# MCU.net
KiCad netlist of a schematic drawn in Altium Designer
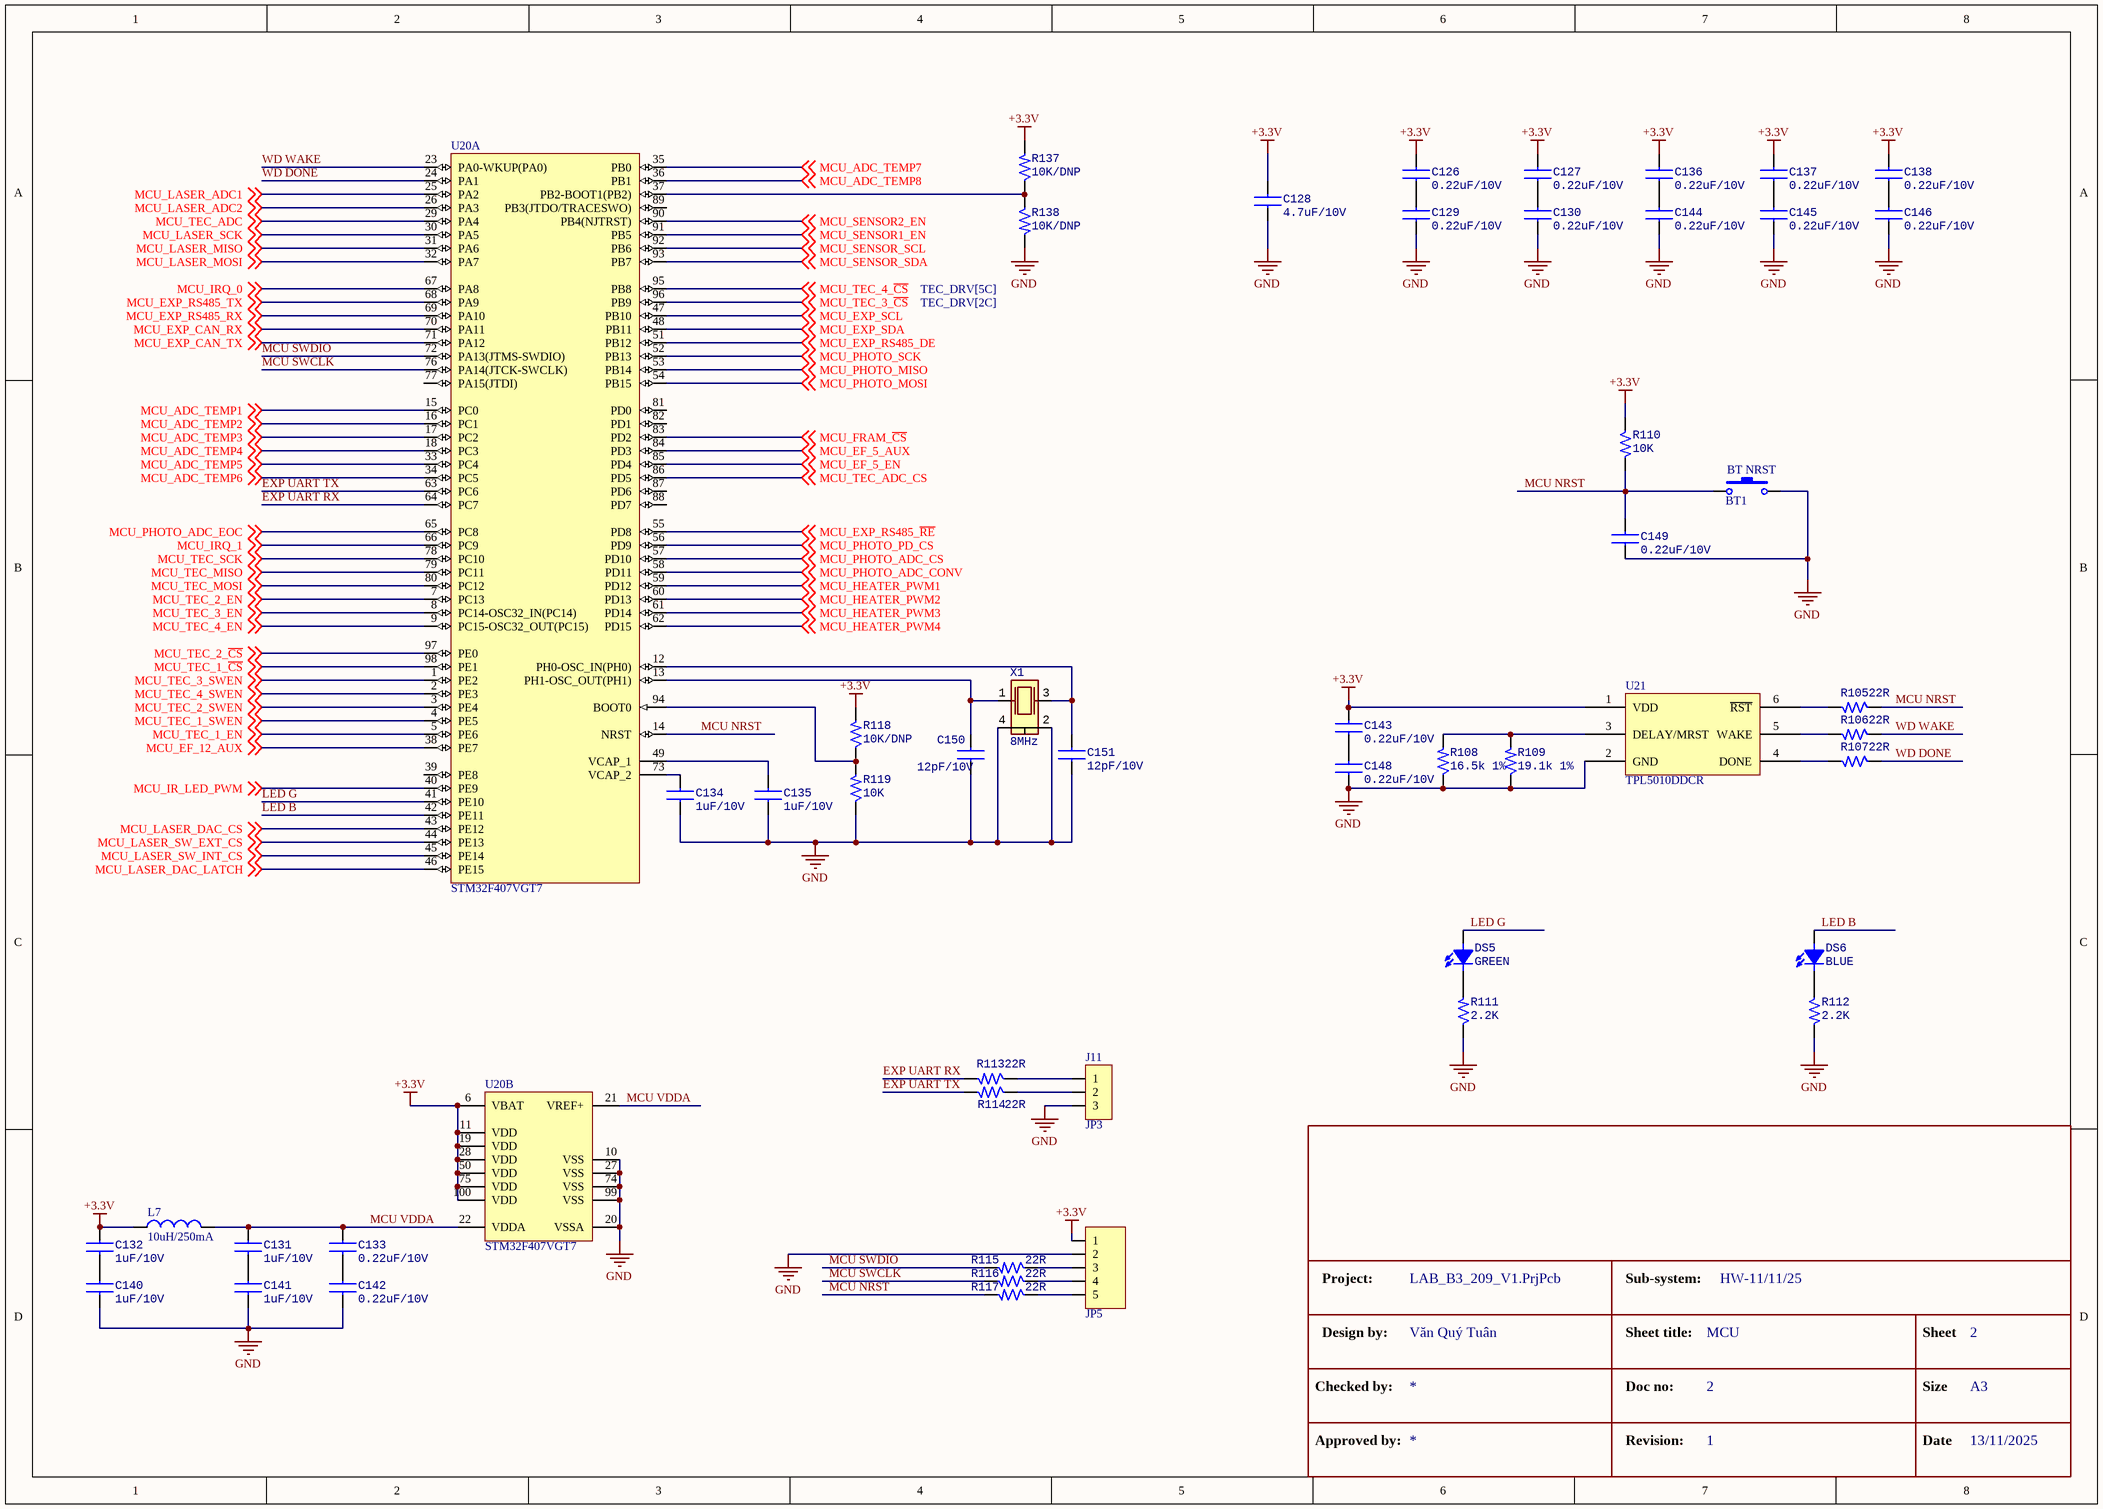
[diagram p0: MCU.SchDoc]

(export (version "E")
  (design (tool "Eeschema 10.0.6"))
  (components
    (comp (ref "BT1")
      (value "BT NRST")
      (footprint "SW-SMD")
      (description "Switch")
      (fields (field (name "PUBLISHER") "Altium Limited"))
      (libsource (lib "Schematic") (part "SW-SMD"))
    )
    (comp (ref "C126")
      (value "0.22uF/10V")
      (footprint "CAP-CER-0603")
      (libsource (lib "ID") (part "CAP-CER"))
    )
    (comp (ref "C127")
      (value "0.22uF/10V")
      (footprint "CAP-CER-0603")
      (libsource (lib "ID") (part "CAP-CER"))
    )
    (comp (ref "C128") (value "4.7uF/10V") (footprint "CAP-CER-0603") (libsource (lib "ID") (part "CAP-CER")))
    (comp (ref "C129")
      (value "0.22uF/10V")
      (footprint "CAP-CER-0603")
      (libsource (lib "ID") (part "CAP-CER"))
    )
    (comp (ref "C130")
      (value "0.22uF/10V")
      (footprint "CAP-CER-0603")
      (libsource (lib "ID") (part "CAP-CER"))
    )
    (comp (ref "C131") (value "1uF/10V") (footprint "CAP-CER-0603") (libsource (lib "ID") (part "CAP-CER")))
    (comp (ref "C132") (value "1uF/10V") (footprint "CAP-CER-0603") (libsource (lib "ID") (part "CAP-CER")))
    (comp (ref "C133")
      (value "0.22uF/10V")
      (footprint "CAP-CER-0603")
      (libsource (lib "ID") (part "CAP-CER"))
    )
    (comp (ref "C134") (value "1uF/10V") (footprint "CAP-CER-0603") (libsource (lib "ID") (part "CAP-CER")))
    (comp (ref "C135") (value "1uF/10V") (footprint "CAP-CER-0603") (libsource (lib "ID") (part "CAP-CER")))
    (comp (ref "C136")
      (value "0.22uF/10V")
      (footprint "CAP-CER-0603")
      (libsource (lib "ID") (part "CAP-CER"))
    )
    (comp (ref "C137")
      (value "0.22uF/10V")
      (footprint "CAP-CER-0603")
      (libsource (lib "ID") (part "CAP-CER"))
    )
    (comp (ref "C138")
      (value "0.22uF/10V")
      (footprint "CAP-CER-0603")
      (libsource (lib "ID") (part "CAP-CER"))
    )
    (comp (ref "C140") (value "1uF/10V") (footprint "CAP-CER-0603") (libsource (lib "ID") (part "CAP-CER")))
    (comp (ref "C141") (value "1uF/10V") (footprint "CAP-CER-0603") (libsource (lib "ID") (part "CAP-CER")))
    (comp (ref "C142")
      (value "0.22uF/10V")
      (footprint "CAP-CER-0603")
      (libsource (lib "ID") (part "CAP-CER"))
    )
    (comp (ref "C143")
      (value "0.22uF/10V")
      (footprint "CAP-CER-0603")
      (libsource (lib "ID") (part "CAP-CER"))
    )
    (comp (ref "C144")
      (value "0.22uF/10V")
      (footprint "CAP-CER-0603")
      (libsource (lib "ID") (part "CAP-CER"))
    )
    (comp (ref "C145")
      (value "0.22uF/10V")
      (footprint "CAP-CER-0603")
      (libsource (lib "ID") (part "CAP-CER"))
    )
    (comp (ref "C146")
      (value "0.22uF/10V")
      (footprint "CAP-CER-0603")
      (libsource (lib "ID") (part "CAP-CER"))
    )
    (comp (ref "C148")
      (value "0.22uF/10V")
      (footprint "CAP-CER-0603")
      (libsource (lib "ID") (part "CAP-CER"))
    )
    (comp (ref "C149")
      (value "0.22uF/10V")
      (footprint "CAP-CER-0603")
      (libsource (lib "ID") (part "CAP-CER"))
    )
    (comp (ref "C150") (value "12pF/10V") (footprint "CAP-CER-0603") (libsource (lib "ID") (part "CAP-CER")))
    (comp (ref "C151") (value "12pF/10V") (footprint "CAP-CER-0603") (libsource (lib "ID") (part "CAP-CER")))
    (comp (ref "DS5") (value "GREEN") (footprint "LED-SMD-0603") (libsource (lib "ID") (part "LED")))
    (comp (ref "DS6") (value "BLUE") (footprint "LED-SMD-0603") (libsource (lib "ID") (part "LED")))
    (comp (ref "J6")
      (value "JP5")
      (footprint "JP 1x5 CT")
      (description "1X5 2.54")
      (libsource (lib "Jump") (part "JP 1x5 2.54 Cai Thang"))
    )
    (comp (ref "J11")
      (value "JP3")
      (footprint "JP 1x3 CT")
      (description "1X3 2.54")
      (libsource (lib "Jump") (part "JP 1x3 2.54 Cai Thang"))
    )
    (comp (ref "L7")
      (value "10uH/250mA")
      (footprint "INDUCT-SMD-0603")
      (fields (field (name "MP") "LQM18PZ2R2MFHD") (field (name "MF") "Murata"))
      (libsource (lib "ID") (part "INDUCT-SMD"))
    )
    (comp (ref "R105") (value "22R") (footprint "RES-SMD-0603") (libsource (lib "ID") (part "RES-SMD")))
    (comp (ref "R106") (value "22R") (footprint "RES-SMD-0603") (libsource (lib "ID") (part "RES-SMD")))
    (comp (ref "R107") (value "22R") (footprint "RES-SMD-0603") (libsource (lib "ID") (part "RES-SMD")))
    (comp (ref "R108") (value "16.5k 1%") (footprint "RES-SMD-0603") (libsource (lib "ID") (part "RES-SMD")))
    (comp (ref "R109") (value "19.1k 1%") (footprint "RES-SMD-0603") (libsource (lib "ID") (part "RES-SMD")))
    (comp (ref "R110") (value "10K") (footprint "RES-SMD-0603") (libsource (lib "ID") (part "RES-SMD")))
    (comp (ref "R111") (value "2.2K") (footprint "RES-SMD-0603") (libsource (lib "ID") (part "RES-SMD")))
    (comp (ref "R112") (value "2.2K") (footprint "RES-SMD-0603") (libsource (lib "ID") (part "RES-SMD")))
    (comp (ref "R113") (value "22R") (footprint "RES-SMD-0603") (libsource (lib "ID") (part "RES-SMD")))
    (comp (ref "R114") (value "22R") (footprint "RES-SMD-0603") (libsource (lib "ID") (part "RES-SMD")))
    (comp (ref "R115") (value "22R") (footprint "RES-SMD-0603") (libsource (lib "ID") (part "RES-SMD")))
    (comp (ref "R116") (value "22R") (footprint "RES-SMD-0603") (libsource (lib "ID") (part "RES-SMD")))
    (comp (ref "R117") (value "22R") (footprint "RES-SMD-0603") (libsource (lib "ID") (part "RES-SMD")))
    (comp (ref "R118") (value "10K/DNP") (footprint "RES-SMD-0603") (libsource (lib "ID") (part "RES-SMD")))
    (comp (ref "R119") (value "10K") (footprint "RES-SMD-0603") (libsource (lib "ID") (part "RES-SMD")))
    (comp (ref "R137") (value "10K/DNP") (footprint "RES-SMD-0603") (libsource (lib "ID") (part "RES-SMD")))
    (comp (ref "R138") (value "10K/DNP") (footprint "RES-SMD-0603") (libsource (lib "ID") (part "RES-SMD")))
    (comp (ref "U20")
      (value "STM32F407VGT7")
      (footprint "STM-LQFP100_V")
      (fields (field (name "MANUFACTURER") "STMicroelectronics"))
      (libsource (lib "STMicroelectronics STM32 F4") (part "STM32F407VGT7"))
    )
    (comp (ref "U21")
      (value "TPL5010DDCR")
      (footprint "TPL5010DDCR")
      (libsource (lib "LAB_B3_209_V1") (part "TPL5010DDCR"))
    )
    (comp (ref "X1")
      (value "8MHz")
      (footprint "CRYSTAL-4POS-3.2x2.5")
      (description "Crystal, 8 MHz, -30 to 85 degC, 3.2 x 2.5 x 0.9 mm SMD")
      (libsource (lib "ID") (part "CRYSTAL-4POS"))
    )
  )
  (nets
    (net (code "1") (name "+3.3V") (class "Default")
      (node (ref "C126") (pin "1") (pinfunction "1_1") (pintype "passive"))
      (node (ref "C127") (pin "1") (pinfunction "1_1") (pintype "passive"))
      (node (ref "C128") (pin "1") (pinfunction "1_1") (pintype "passive"))
      (node (ref "C132") (pin "1") (pinfunction "1_1") (pintype "passive"))
      (node (ref "C136") (pin "1") (pinfunction "1_1") (pintype "passive"))
      (node (ref "C137") (pin "1") (pinfunction "1_1") (pintype "passive"))
      (node (ref "C138") (pin "1") (pinfunction "1_1") (pintype "passive"))
      (node (ref "C143") (pin "1") (pinfunction "1_1") (pintype "passive"))
      (node (ref "J6") (pin "1") (pinfunction "1_1") (pintype "passive"))
      (node (ref "L7") (pin "1") (pinfunction "1_1") (pintype "passive"))
      (node (ref "R110") (pin "1") (pinfunction "1_1") (pintype "passive"))
      (node (ref "R118") (pin "2") (pinfunction "2_2") (pintype "passive"))
      (node (ref "R137") (pin "2") (pinfunction "2_2") (pintype "passive"))
      (node (ref "U20") (pin "100") (pinfunction "VDD_100") (pintype "power_in"))
      (node (ref "U20") (pin "11") (pinfunction "VDD_11") (pintype "power_in"))
      (node (ref "U20") (pin "19") (pinfunction "VDD_19") (pintype "power_in"))
      (node (ref "U20") (pin "28") (pinfunction "VDD_28") (pintype "power_in"))
      (node (ref "U20") (pin "50") (pinfunction "VDD_50") (pintype "power_in"))
      (node (ref "U20") (pin "6") (pinfunction "VBAT_6") (pintype "power_in"))
      (node (ref "U20") (pin "75") (pinfunction "VDD_75") (pintype "power_in"))
      (node (ref "U21") (pin "1") (pinfunction "VDD_1") (pintype "passive"))
    )
    (net (code "2") (name "/EXP UART RX") (class "Default")
      (node (ref "R113") (pin "2") (pinfunction "2_2") (pintype "passive"))
      (node (ref "U20") (pin "64") (pinfunction "PC7_64") (pintype "bidirectional"))
    )
    (net (code "3") (name "/EXP UART TX") (class "Default")
      (node (ref "R114") (pin "2") (pinfunction "2_2") (pintype "passive"))
      (node (ref "U20") (pin "63") (pinfunction "PC6_63") (pintype "bidirectional"))
    )
    (net (code "4") (name "/LED B") (class "Default")
      (node (ref "DS6") (pin "A") (pinfunction "A_A") (pintype "passive"))
      (node (ref "U20") (pin "42") (pinfunction "PE11_42") (pintype "bidirectional"))
    )
    (net (code "5") (name "/LED G") (class "Default")
      (node (ref "DS5") (pin "A") (pinfunction "A_A") (pintype "passive"))
      (node (ref "U20") (pin "41") (pinfunction "PE10_41") (pintype "bidirectional"))
    )
    (net (code "6") (name "/MCU NRST") (class "Default")
      (node (ref "BT1") (pin "1") (pinfunction "1_1") (pintype "passive"))
      (node (ref "C149") (pin "1") (pinfunction "1_1") (pintype "passive"))
      (node (ref "R105") (pin "1") (pinfunction "1_1") (pintype "passive"))
      (node (ref "R110") (pin "2") (pinfunction "2_2") (pintype "passive"))
      (node (ref "R117") (pin "2") (pinfunction "2_2") (pintype "passive"))
      (node (ref "U20") (pin "14") (pinfunction "NRST_14") (pintype "bidirectional"))
    )
    (net (code "7") (name "/MCU SWCLK") (class "Default")
      (node (ref "R116") (pin "2") (pinfunction "2_2") (pintype "passive"))
      (node (ref "U20") (pin "76") (pinfunction "PA14(JTCK-SWCLK)_76") (pintype "bidirectional"))
    )
    (net (code "8") (name "/MCU SWDIO") (class "Default")
      (node (ref "R115") (pin "2") (pinfunction "2_2") (pintype "passive"))
      (node (ref "U20") (pin "72") (pinfunction "PA13(JTMS-SWDIO)_72") (pintype "bidirectional"))
    )
    (net (code "9") (name "/MCU VDDA") (class "Default")
      (node (ref "C131") (pin "1") (pinfunction "1_1") (pintype "passive"))
      (node (ref "C133") (pin "1") (pinfunction "1_1") (pintype "passive"))
      (node (ref "L7") (pin "2") (pinfunction "2_2") (pintype "passive"))
      (node (ref "U20") (pin "21") (pinfunction "VREF+_21") (pintype "power_in"))
      (node (ref "U20") (pin "22") (pinfunction "VDDA_22") (pintype "power_in"))
    )
    (net (code "10") (name "/WD DONE") (class "Default")
      (node (ref "R107") (pin "1") (pinfunction "1_1") (pintype "passive"))
      (node (ref "U20") (pin "24") (pinfunction "PA1_24") (pintype "bidirectional"))
    )
    (net (code "11") (name "/WD WAKE") (class "Default")
      (node (ref "R106") (pin "1") (pinfunction "1_1") (pintype "passive"))
      (node (ref "U20") (pin "23") (pinfunction "PA0-WKUP(PA0)_23") (pintype "bidirectional"))
    )
    (net (code "12") (name "GND") (class "Default")
      (node (ref "BT1") (pin "2") (pinfunction "2_2") (pintype "passive"))
      (node (ref "C128") (pin "2") (pinfunction "2_2") (pintype "passive"))
      (node (ref "C129") (pin "2") (pinfunction "2_2") (pintype "passive"))
      (node (ref "C130") (pin "2") (pinfunction "2_2") (pintype "passive"))
      (node (ref "C134") (pin "2") (pinfunction "2_2") (pintype "passive"))
      (node (ref "C135") (pin "2") (pinfunction "2_2") (pintype "passive"))
      (node (ref "C140") (pin "2") (pinfunction "2_2") (pintype "passive"))
      (node (ref "C141") (pin "2") (pinfunction "2_2") (pintype "passive"))
      (node (ref "C142") (pin "2") (pinfunction "2_2") (pintype "passive"))
      (node (ref "C144") (pin "2") (pinfunction "2_2") (pintype "passive"))
      (node (ref "C145") (pin "2") (pinfunction "2_2") (pintype "passive"))
      (node (ref "C146") (pin "2") (pinfunction "2_2") (pintype "passive"))
      (node (ref "C148") (pin "2") (pinfunction "2_2") (pintype "passive"))
      (node (ref "C149") (pin "2") (pinfunction "2_2") (pintype "passive"))
      (node (ref "C150") (pin "2") (pinfunction "2_2") (pintype "passive"))
      (node (ref "C151") (pin "2") (pinfunction "2_2") (pintype "passive"))
      (node (ref "J11") (pin "3") (pinfunction "3_3") (pintype "passive"))
      (node (ref "J6") (pin "2") (pinfunction "2_2") (pintype "passive"))
      (node (ref "R108") (pin "1") (pinfunction "1_1") (pintype "passive"))
      (node (ref "R109") (pin "1") (pinfunction "1_1") (pintype "passive"))
      (node (ref "R111") (pin "1") (pinfunction "1_1") (pintype "passive"))
      (node (ref "R112") (pin "2") (pinfunction "2_2") (pintype "passive"))
      (node (ref "R119") (pin "1") (pinfunction "1_1") (pintype "passive"))
      (node (ref "R138") (pin "2") (pinfunction "2_2") (pintype "passive"))
      (node (ref "U20") (pin "10") (pinfunction "VSS_10") (pintype "power_in"))
      (node (ref "U20") (pin "20") (pinfunction "VSSA_20") (pintype "power_in"))
      (node (ref "U20") (pin "27") (pinfunction "VSS_27") (pintype "power_in"))
      (node (ref "U20") (pin "74") (pinfunction "VSS_74") (pintype "power_in"))
      (node (ref "U20") (pin "99") (pinfunction "VSS_99") (pintype "power_in"))
      (node (ref "U21") (pin "2") (pinfunction "GND_2") (pintype "passive"))
      (node (ref "X1") (pin "2") (pinfunction "2_2") (pintype "passive"))
      (node (ref "X1") (pin "4") (pinfunction "4_4") (pintype "passive"))
    )
    (net (code "13") (name "MCU_ADC_TEMP1") (class "Default")
      (node (ref "U20") (pin "15") (pinfunction "PC0_15") (pintype "bidirectional"))
    )
    (net (code "14") (name "MCU_ADC_TEMP2") (class "Default")
      (node (ref "U20") (pin "16") (pinfunction "PC1_16") (pintype "bidirectional"))
    )
    (net (code "15") (name "MCU_ADC_TEMP3") (class "Default")
      (node (ref "U20") (pin "17") (pinfunction "PC2_17") (pintype "bidirectional"))
    )
    (net (code "16") (name "MCU_ADC_TEMP4") (class "Default")
      (node (ref "U20") (pin "18") (pinfunction "PC3_18") (pintype "bidirectional"))
    )
    (net (code "17") (name "MCU_ADC_TEMP5") (class "Default")
      (node (ref "U20") (pin "33") (pinfunction "PC4_33") (pintype "bidirectional"))
    )
    (net (code "18") (name "MCU_ADC_TEMP6") (class "Default")
      (node (ref "U20") (pin "34") (pinfunction "PC5_34") (pintype "bidirectional"))
    )
    (net (code "19") (name "MCU_ADC_TEMP7") (class "Default")
      (node (ref "U20") (pin "35") (pinfunction "PB0_35") (pintype "bidirectional"))
    )
    (net (code "20") (name "MCU_ADC_TEMP8") (class "Default")
      (node (ref "U20") (pin "36") (pinfunction "PB1_36") (pintype "bidirectional"))
    )
    (net (code "21") (name "MCU_EF_5_AUX") (class "Default")
      (node (ref "U20") (pin "84") (pinfunction "PD3_84") (pintype "bidirectional"))
    )
    (net (code "22") (name "MCU_EF_5_EN") (class "Default")
      (node (ref "U20") (pin "85") (pinfunction "PD4_85") (pintype "bidirectional"))
    )
    (net (code "23") (name "MCU_EF_12_AUX") (class "Default")
      (node (ref "U20") (pin "38") (pinfunction "PE7_38") (pintype "bidirectional"))
    )
    (net (code "24") (name "MCU_EXP_CAN_RX") (class "Default")
      (node (ref "U20") (pin "70") (pinfunction "PA11_70") (pintype "bidirectional"))
    )
    (net (code "25") (name "MCU_EXP_CAN_TX") (class "Default")
      (node (ref "U20") (pin "71") (pinfunction "PA12_71") (pintype "bidirectional"))
    )
    (net (code "26") (name "MCU_EXP_RS485_DE") (class "Default")
      (node (ref "U20") (pin "51") (pinfunction "PB12_51") (pintype "bidirectional"))
    )
    (net (code "27") (name "MCU_EXP_RS485_RX") (class "Default")
      (node (ref "U20") (pin "69") (pinfunction "PA10_69") (pintype "bidirectional"))
    )
    (net (code "28") (name "MCU_EXP_RS485_TX") (class "Default")
      (node (ref "U20") (pin "68") (pinfunction "PA9_68") (pintype "bidirectional"))
    )
    (net (code "29") (name "MCU_EXP_RS485_~{RE}") (class "Default")
      (node (ref "U20") (pin "55") (pinfunction "PD8_55") (pintype "bidirectional"))
    )
    (net (code "30") (name "MCU_EXP_SCL") (class "Default")
      (node (ref "U20") (pin "47") (pinfunction "PB10_47") (pintype "bidirectional"))
    )
    (net (code "31") (name "MCU_EXP_SDA") (class "Default")
      (node (ref "U20") (pin "48") (pinfunction "PB11_48") (pintype "bidirectional"))
    )
    (net (code "32") (name "MCU_FRAM_~{CS}") (class "Default")
      (node (ref "U20") (pin "83") (pinfunction "PD2_83") (pintype "bidirectional"))
    )
    (net (code "33") (name "MCU_HEATER_PWM1") (class "Default")
      (node (ref "U20") (pin "59") (pinfunction "PD12_59") (pintype "bidirectional"))
    )
    (net (code "34") (name "MCU_HEATER_PWM2") (class "Default")
      (node (ref "U20") (pin "60") (pinfunction "PD13_60") (pintype "bidirectional"))
    )
    (net (code "35") (name "MCU_HEATER_PWM3") (class "Default")
      (node (ref "U20") (pin "61") (pinfunction "PD14_61") (pintype "bidirectional"))
    )
    (net (code "36") (name "MCU_HEATER_PWM4") (class "Default")
      (node (ref "U20") (pin "62") (pinfunction "PD15_62") (pintype "bidirectional"))
    )
    (net (code "37") (name "MCU_IRQ_0") (class "Default")
      (node (ref "U20") (pin "67") (pinfunction "PA8_67") (pintype "bidirectional"))
    )
    (net (code "38") (name "MCU_IRQ_1") (class "Default")
      (node (ref "U20") (pin "66") (pinfunction "PC9_66") (pintype "bidirectional"))
    )
    (net (code "39") (name "MCU_IR_LED_PWM") (class "Default")
      (node (ref "U20") (pin "40") (pinfunction "PE9_40") (pintype "bidirectional"))
    )
    (net (code "40") (name "MCU_LASER_ADC1") (class "Default")
      (node (ref "U20") (pin "25") (pinfunction "PA2_25") (pintype "bidirectional"))
    )
    (net (code "41") (name "MCU_LASER_ADC2") (class "Default")
      (node (ref "U20") (pin "26") (pinfunction "PA3_26") (pintype "bidirectional"))
    )
    (net (code "42") (name "MCU_LASER_DAC_CS") (class "Default")
      (node (ref "U20") (pin "43") (pinfunction "PE12_43") (pintype "bidirectional"))
    )
    (net (code "43") (name "MCU_LASER_DAC_LATCH") (class "Default")
      (node (ref "U20") (pin "46") (pinfunction "PE15_46") (pintype "bidirectional"))
    )
    (net (code "44") (name "MCU_LASER_MISO") (class "Default")
      (node (ref "U20") (pin "31") (pinfunction "PA6_31") (pintype "bidirectional"))
    )
    (net (code "45") (name "MCU_LASER_MOSI") (class "Default")
      (node (ref "U20") (pin "32") (pinfunction "PA7_32") (pintype "bidirectional"))
    )
    (net (code "46") (name "MCU_LASER_SCK") (class "Default")
      (node (ref "U20") (pin "30") (pinfunction "PA5_30") (pintype "bidirectional"))
    )
    (net (code "47") (name "MCU_LASER_SW_EXT_CS") (class "Default")
      (node (ref "U20") (pin "44") (pinfunction "PE13_44") (pintype "bidirectional"))
    )
    (net (code "48") (name "MCU_LASER_SW_INT_CS") (class "Default")
      (node (ref "U20") (pin "45") (pinfunction "PE14_45") (pintype "bidirectional"))
    )
    (net (code "49") (name "MCU_PHOTO_ADC_CONV") (class "Default")
      (node (ref "U20") (pin "58") (pinfunction "PD11_58") (pintype "bidirectional"))
    )
    (net (code "50") (name "MCU_PHOTO_ADC_CS") (class "Default")
      (node (ref "U20") (pin "57") (pinfunction "PD10_57") (pintype "bidirectional"))
    )
    (net (code "51") (name "MCU_PHOTO_ADC_EOC") (class "Default")
      (node (ref "U20") (pin "65") (pinfunction "PC8_65") (pintype "bidirectional"))
    )
    (net (code "52") (name "MCU_PHOTO_MISO") (class "Default")
      (node (ref "U20") (pin "53") (pinfunction "PB14_53") (pintype "bidirectional"))
    )
    (net (code "53") (name "MCU_PHOTO_MOSI") (class "Default")
      (node (ref "U20") (pin "54") (pinfunction "PB15_54") (pintype "bidirectional"))
    )
    (net (code "54") (name "MCU_PHOTO_PD_CS") (class "Default")
      (node (ref "U20") (pin "56") (pinfunction "PD9_56") (pintype "bidirectional"))
    )
    (net (code "55") (name "MCU_PHOTO_SCK") (class "Default")
      (node (ref "U20") (pin "52") (pinfunction "PB13_52") (pintype "bidirectional"))
    )
    (net (code "56") (name "MCU_SENSOR1_EN") (class "Default")
      (node (ref "U20") (pin "91") (pinfunction "PB5_91") (pintype "bidirectional"))
    )
    (net (code "57") (name "MCU_SENSOR2_EN") (class "Default")
      (node (ref "U20") (pin "90") (pinfunction "PB4(NJTRST)_90") (pintype "bidirectional"))
    )
    (net (code "58") (name "MCU_SENSOR_SCL") (class "Default")
      (node (ref "U20") (pin "92") (pinfunction "PB6_92") (pintype "bidirectional"))
    )
    (net (code "59") (name "MCU_SENSOR_SDA") (class "Default")
      (node (ref "U20") (pin "93") (pinfunction "PB7_93") (pintype "bidirectional"))
    )
    (net (code "60") (name "MCU_TEC_1_EN") (class "Default")
      (node (ref "U20") (pin "5") (pinfunction "PE6_5") (pintype "bidirectional"))
    )
    (net (code "61") (name "MCU_TEC_1_SWEN") (class "Default")
      (node (ref "U20") (pin "4") (pinfunction "PE5_4") (pintype "bidirectional"))
    )
    (net (code "62") (name "MCU_TEC_1_~{CS}") (class "Default")
      (node (ref "U20") (pin "98") (pinfunction "PE1_98") (pintype "bidirectional"))
    )
    (net (code "63") (name "MCU_TEC_2_EN") (class "Default")
      (node (ref "U20") (pin "7") (pinfunction "PC13_7") (pintype "bidirectional"))
    )
    (net (code "64") (name "MCU_TEC_2_SWEN") (class "Default")
      (node (ref "U20") (pin "3") (pinfunction "PE4_3") (pintype "bidirectional"))
    )
    (net (code "65") (name "MCU_TEC_2_~{CS}") (class "Default")
      (node (ref "U20") (pin "97") (pinfunction "PE0_97") (pintype "bidirectional"))
    )
    (net (code "66") (name "MCU_TEC_3_EN") (class "Default")
      (node (ref "U20") (pin "8") (pinfunction "PC14-OSC32_IN(PC14)_8") (pintype "bidirectional"))
    )
    (net (code "67") (name "MCU_TEC_3_SWEN") (class "Default")
      (node (ref "U20") (pin "1") (pinfunction "PE2_1") (pintype "bidirectional"))
    )
    (net (code "68") (name "MCU_TEC_3_~{CS}") (class "Default")
      (node (ref "U20") (pin "96") (pinfunction "PB9_96") (pintype "bidirectional"))
    )
    (net (code "69") (name "MCU_TEC_4_EN") (class "Default")
      (node (ref "U20") (pin "9") (pinfunction "PC15-OSC32_OUT(PC15)_9") (pintype "bidirectional"))
    )
    (net (code "70") (name "MCU_TEC_4_SWEN") (class "Default")
      (node (ref "U20") (pin "2") (pinfunction "PE3_2") (pintype "bidirectional"))
    )
    (net (code "71") (name "MCU_TEC_4_~{CS}") (class "Default")
      (node (ref "U20") (pin "95") (pinfunction "PB8_95") (pintype "bidirectional"))
    )
    (net (code "72") (name "MCU_TEC_ADC") (class "Default")
      (node (ref "U20") (pin "29") (pinfunction "PA4_29") (pintype "bidirectional"))
    )
    (net (code "73") (name "MCU_TEC_ADC_CS") (class "Default")
      (node (ref "U20") (pin "86") (pinfunction "PD5_86") (pintype "bidirectional"))
    )
    (net (code "74") (name "MCU_TEC_MISO") (class "Default")
      (node (ref "U20") (pin "79") (pinfunction "PC11_79") (pintype "bidirectional"))
    )
    (net (code "75") (name "MCU_TEC_MOSI") (class "Default")
      (node (ref "U20") (pin "80") (pinfunction "PC12_80") (pintype "bidirectional"))
    )
    (net (code "76") (name "MCU_TEC_SCK") (class "Default")
      (node (ref "U20") (pin "78") (pinfunction "PC10_78") (pintype "bidirectional"))
    )
    (net (code "77") (name "Net-(C126-Pad2)") (class "Default")
      (node (ref "C126") (pin "2") (pinfunction "2_2") (pintype "passive"))
      (node (ref "C129") (pin "1") (pinfunction "1_1") (pintype "passive"))
    )
    (net (code "78") (name "Net-(C127-Pad2)") (class "Default")
      (node (ref "C127") (pin "2") (pinfunction "2_2") (pintype "passive"))
      (node (ref "C130") (pin "1") (pinfunction "1_1") (pintype "passive"))
    )
    (net (code "79") (name "Net-(C131-Pad2)") (class "Default")
      (node (ref "C131") (pin "2") (pinfunction "2_2") (pintype "passive"))
      (node (ref "C141") (pin "1") (pinfunction "1_1") (pintype "passive"))
    )
    (net (code "80") (name "Net-(C132-Pad2)") (class "Default")
      (node (ref "C132") (pin "2") (pinfunction "2_2") (pintype "passive"))
      (node (ref "C140") (pin "1") (pinfunction "1_1") (pintype "passive"))
    )
    (net (code "81") (name "Net-(C133-Pad2)") (class "Default")
      (node (ref "C133") (pin "2") (pinfunction "2_2") (pintype "passive"))
      (node (ref "C142") (pin "1") (pinfunction "1_1") (pintype "passive"))
    )
    (net (code "82") (name "Net-(C136-Pad2)") (class "Default")
      (node (ref "C136") (pin "2") (pinfunction "2_2") (pintype "passive"))
      (node (ref "C144") (pin "1") (pinfunction "1_1") (pintype "passive"))
    )
    (net (code "83") (name "Net-(C137-Pad2)") (class "Default")
      (node (ref "C137") (pin "2") (pinfunction "2_2") (pintype "passive"))
      (node (ref "C145") (pin "1") (pinfunction "1_1") (pintype "passive"))
    )
    (net (code "84") (name "Net-(C138-Pad2)") (class "Default")
      (node (ref "C138") (pin "2") (pinfunction "2_2") (pintype "passive"))
      (node (ref "C146") (pin "1") (pinfunction "1_1") (pintype "passive"))
    )
    (net (code "85") (name "Net-(C143-Pad2)") (class "Default")
      (node (ref "C143") (pin "2") (pinfunction "2_2") (pintype "passive"))
      (node (ref "C148") (pin "1") (pinfunction "1_1") (pintype "passive"))
    )
    (net (code "86") (name "Net-(DS5-PadK)") (class "Default")
      (node (ref "DS5") (pin "K") (pinfunction "K_K") (pintype "passive"))
      (node (ref "R111") (pin "2") (pinfunction "2_2") (pintype "passive"))
    )
    (net (code "87") (name "Net-(DS6-PadK)") (class "Default")
      (node (ref "DS6") (pin "K") (pinfunction "K_K") (pintype "passive"))
      (node (ref "R112") (pin "1") (pinfunction "1_1") (pintype "passive"))
    )
    (net (code "88") (name "Net-(J6-Pad3)") (class "Default")
      (node (ref "J6") (pin "3") (pinfunction "3_3") (pintype "passive"))
      (node (ref "R115") (pin "1") (pinfunction "1_1") (pintype "passive"))
    )
    (net (code "89") (name "Net-(J6-Pad4)") (class "Default")
      (node (ref "J6") (pin "4") (pinfunction "4_4") (pintype "passive"))
      (node (ref "R116") (pin "1") (pinfunction "1_1") (pintype "passive"))
    )
    (net (code "90") (name "Net-(J6-Pad5)") (class "Default")
      (node (ref "J6") (pin "5") (pinfunction "5_5") (pintype "passive"))
      (node (ref "R117") (pin "1") (pinfunction "1_1") (pintype "passive"))
    )
    (net (code "91") (name "Net-(J11-Pad1)") (class "Default")
      (node (ref "J11") (pin "1") (pinfunction "1_1") (pintype "passive"))
      (node (ref "R113") (pin "1") (pinfunction "1_1") (pintype "passive"))
    )
    (net (code "92") (name "Net-(J11-Pad2)") (class "Default")
      (node (ref "J11") (pin "2") (pinfunction "2_2") (pintype "passive"))
      (node (ref "R114") (pin "1") (pinfunction "1_1") (pintype "passive"))
    )
    (net (code "93") (name "Net-(U20A-BOOT0)") (class "Default")
      (node (ref "R118") (pin "1") (pinfunction "1_1") (pintype "passive"))
      (node (ref "R119") (pin "2") (pinfunction "2_2") (pintype "passive"))
      (node (ref "U20") (pin "94") (pinfunction "BOOT0_94") (pintype "input"))
    )
    (net (code "94") (name "Net-(U20A-PB2-BOOT1(PB2))") (class "Default")
      (node (ref "R137") (pin "1") (pinfunction "1_1") (pintype "passive"))
      (node (ref "R138") (pin "1") (pinfunction "1_1") (pintype "passive"))
      (node (ref "U20") (pin "37") (pinfunction "PB2-BOOT1(PB2)_37") (pintype "bidirectional"))
    )
    (net (code "95") (name "Net-(U20A-PH0-OSC_IN(PH0))") (class "Default")
      (node (ref "C151") (pin "1") (pinfunction "1_1") (pintype "passive"))
      (node (ref "U20") (pin "12") (pinfunction "PH0-OSC_IN(PH0)_12") (pintype "bidirectional"))
      (node (ref "X1") (pin "3") (pinfunction "3_3") (pintype "passive"))
    )
    (net (code "96") (name "Net-(U20A-PH1-OSC_OUT(PH1))") (class "Default")
      (node (ref "C150") (pin "1") (pinfunction "1_1") (pintype "passive"))
      (node (ref "U20") (pin "13") (pinfunction "PH1-OSC_OUT(PH1)_13") (pintype "bidirectional"))
      (node (ref "X1") (pin "1") (pinfunction "1_1") (pintype "passive"))
    )
    (net (code "97") (name "Net-(U20A-VCAP_1)") (class "Default")
      (node (ref "C135") (pin "1") (pinfunction "1_1") (pintype "passive"))
      (node (ref "U20") (pin "49") (pinfunction "VCAP_1_49") (pintype "power_in"))
    )
    (net (code "98") (name "Net-(U20A-VCAP_2)") (class "Default")
      (node (ref "C134") (pin "1") (pinfunction "1_1") (pintype "passive"))
      (node (ref "U20") (pin "73") (pinfunction "VCAP_2_73") (pintype "power_in"))
    )
    (net (code "99") (name "Net-(U21-DELAY{slash}MRST)") (class "Default")
      (node (ref "R108") (pin "2") (pinfunction "2_2") (pintype "passive"))
      (node (ref "R109") (pin "2") (pinfunction "2_2") (pintype "passive"))
      (node (ref "U21") (pin "3") (pinfunction "DELAY/MRST_3") (pintype "passive"))
    )
    (net (code "100") (name "Net-(U21-DONE)") (class "Default")
      (node (ref "R107") (pin "2") (pinfunction "2_2") (pintype "passive"))
      (node (ref "U21") (pin "4") (pinfunction "DONE_4") (pintype "passive"))
    )
    (net (code "101") (name "Net-(U21-WAKE)") (class "Default")
      (node (ref "R106") (pin "2") (pinfunction "2_2") (pintype "passive"))
      (node (ref "U21") (pin "5") (pinfunction "WAKE_5") (pintype "passive"))
    )
    (net (code "102") (name "Net-(U21-~{RST})") (class "Default")
      (node (ref "R105") (pin "2") (pinfunction "2_2") (pintype "passive"))
      (node (ref "U21") (pin "6") (pinfunction "~{RST}_6") (pintype "passive"))
    )
    (net (code "103") (name "unconnected-(U20A-PA15(JTDI)-Pad77)") (class "Default")
      (node (ref "U20") (pin "77") (pinfunction "PA15(JTDI)_77") (pintype "bidirectional"))
    )
    (net (code "104") (name "unconnected-(U20A-PB3(JTDO{slash}TRACESWO)-Pad89)") (class "Default")
      (node (ref "U20") (pin "89") (pinfunction "PB3(JTDO/TRACESWO)_89") (pintype "bidirectional"))
    )
    (net (code "105") (name "unconnected-(U20A-PD0-Pad81)") (class "Default")
      (node (ref "U20") (pin "81") (pinfunction "PD0_81") (pintype "bidirectional"))
    )
    (net (code "106") (name "unconnected-(U20A-PD1-Pad82)") (class "Default")
      (node (ref "U20") (pin "82") (pinfunction "PD1_82") (pintype "bidirectional"))
    )
    (net (code "107") (name "unconnected-(U20A-PD6-Pad87)") (class "Default")
      (node (ref "U20") (pin "87") (pinfunction "PD6_87") (pintype "bidirectional"))
    )
    (net (code "108") (name "unconnected-(U20A-PD7-Pad88)") (class "Default")
      (node (ref "U20") (pin "88") (pinfunction "PD7_88") (pintype "bidirectional"))
    )
    (net (code "109") (name "unconnected-(U20A-PE8-Pad39)") (class "Default")
      (node (ref "U20") (pin "39") (pinfunction "PE8_39") (pintype "bidirectional"))
    )
  )
)
